# audio_mixer.net
KiCad netlist of a schematic drawn in EAGLE
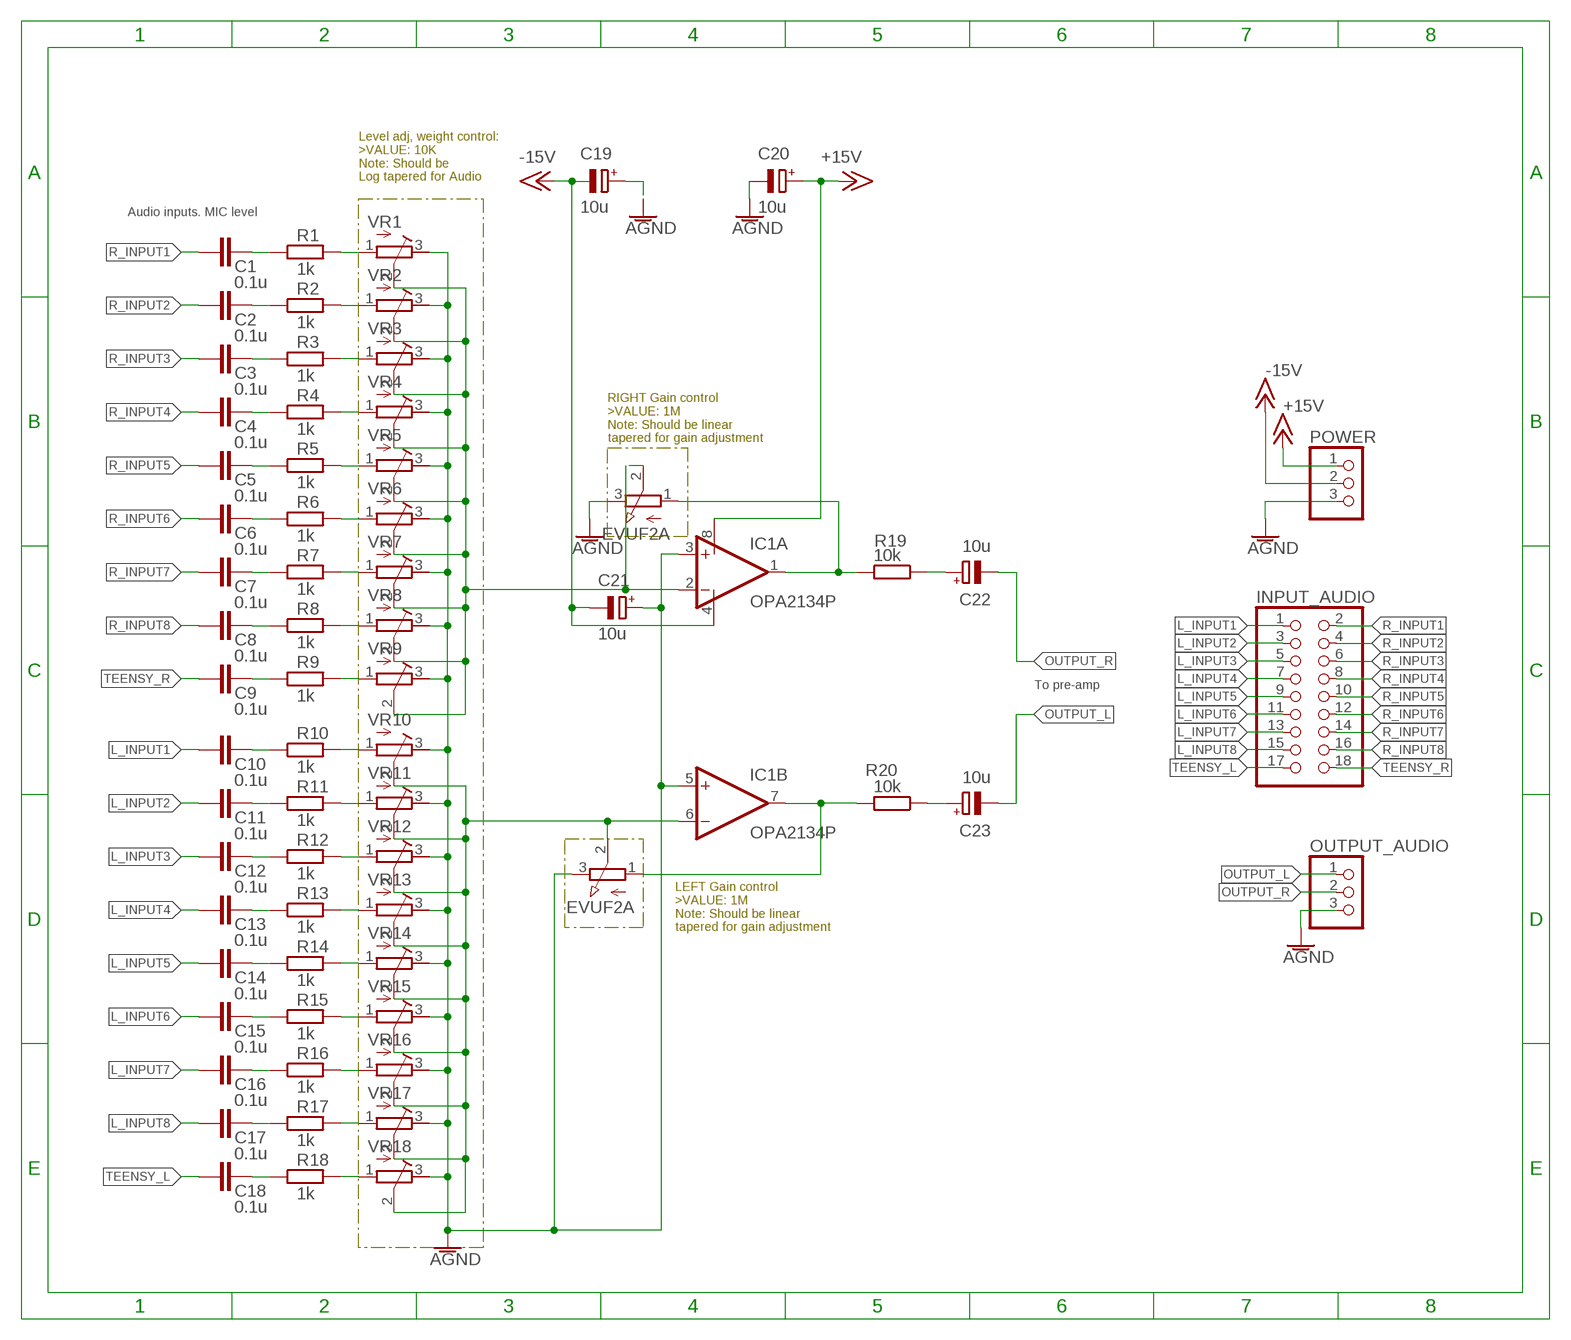
[diagram p0: schematic, sheet 1]

(export (version "E")
  (design (tool "Eeschema 10.0.6"))
  (components
    (comp (ref "C1")
      (value "0.1u")
      (footprint "eagle-import:C025-030X050")
      (libsource (lib "eagle-import") (part "C-EU025-030X050"))
    )
    (comp (ref "C2")
      (value "0.1u")
      (footprint "eagle-import:C025-030X050")
      (libsource (lib "eagle-import") (part "C-EU025-030X050"))
    )
    (comp (ref "C3")
      (value "0.1u")
      (footprint "eagle-import:C025-030X050")
      (libsource (lib "eagle-import") (part "C-EU025-030X050"))
    )
    (comp (ref "C4")
      (value "0.1u")
      (footprint "eagle-import:C025-030X050")
      (libsource (lib "eagle-import") (part "C-EU025-030X050"))
    )
    (comp (ref "C5")
      (value "0.1u")
      (footprint "eagle-import:C025-030X050")
      (libsource (lib "eagle-import") (part "C-EU025-030X050"))
    )
    (comp (ref "C6")
      (value "0.1u")
      (footprint "eagle-import:C025-030X050")
      (libsource (lib "eagle-import") (part "C-EU025-030X050"))
    )
    (comp (ref "C7")
      (value "0.1u")
      (footprint "eagle-import:C025-030X050")
      (libsource (lib "eagle-import") (part "C-EU025-030X050"))
    )
    (comp (ref "C8")
      (value "0.1u")
      (footprint "eagle-import:C025-030X050")
      (libsource (lib "eagle-import") (part "C-EU025-030X050"))
    )
    (comp (ref "C9")
      (value "0.1u")
      (footprint "eagle-import:C025-030X050")
      (libsource (lib "eagle-import") (part "C-EU025-030X050"))
    )
    (comp (ref "C10")
      (value "0.1u")
      (footprint "eagle-import:C025-030X050")
      (libsource (lib "eagle-import") (part "C-EU025-030X050"))
    )
    (comp (ref "C11")
      (value "0.1u")
      (footprint "eagle-import:C025-030X050")
      (libsource (lib "eagle-import") (part "C-EU025-030X050"))
    )
    (comp (ref "C12")
      (value "0.1u")
      (footprint "eagle-import:C025-030X050")
      (libsource (lib "eagle-import") (part "C-EU025-030X050"))
    )
    (comp (ref "C13")
      (value "0.1u")
      (footprint "eagle-import:C025-030X050")
      (libsource (lib "eagle-import") (part "C-EU025-030X050"))
    )
    (comp (ref "C14")
      (value "0.1u")
      (footprint "eagle-import:C025-030X050")
      (libsource (lib "eagle-import") (part "C-EU025-030X050"))
    )
    (comp (ref "C15")
      (value "0.1u")
      (footprint "eagle-import:C025-030X050")
      (libsource (lib "eagle-import") (part "C-EU025-030X050"))
    )
    (comp (ref "C16")
      (value "0.1u")
      (footprint "eagle-import:C025-030X050")
      (libsource (lib "eagle-import") (part "C-EU025-030X050"))
    )
    (comp (ref "C17")
      (value "0.1u")
      (footprint "eagle-import:C025-030X050")
      (libsource (lib "eagle-import") (part "C-EU025-030X050"))
    )
    (comp (ref "C18")
      (value "0.1u")
      (footprint "eagle-import:C025-030X050")
      (libsource (lib "eagle-import") (part "C-EU025-030X050"))
    )
    (comp (ref "C19")
      (value "10u")
      (footprint "eagle-import:E5-10,5")
      (libsource (lib "eagle-import") (part "CPOL-EUE5-10.5"))
    )
    (comp (ref "C20")
      (value "10u")
      (footprint "eagle-import:E5-10,5")
      (libsource (lib "eagle-import") (part "CPOL-EUE5-10.5"))
    )
    (comp (ref "C21")
      (value "10u")
      (footprint "eagle-import:E5-10,5")
      (libsource (lib "eagle-import") (part "CPOL-EUE5-10.5"))
    )
    (comp (ref "C22")
      (value "10u")
      (footprint "eagle-import:E5-10,5")
      (libsource (lib "eagle-import") (part "CPOL-EUE5-10.5"))
    )
    (comp (ref "C23")
      (value "10u")
      (footprint "eagle-import:E5-10,5")
      (libsource (lib "eagle-import") (part "CPOL-EUE5-10.5"))
    )
    (comp (ref "IC1")
      (value "OPA2134P")
      (footprint "eagle-import:DIL08")
      (libsource (lib "eagle-import") (part "OPA2134P"))
    )
    (comp (ref "INPUT_AUDIO")
      (value "PINHD-2X9")
      (footprint "eagle-import:2X09")
      (libsource (lib "eagle-import") (part "PINHD-2X9"))
    )
    (comp (ref "OUTPUT_AUDIO")
      (value "PINHD-1X3")
      (footprint "eagle-import:1X03")
      (libsource (lib "eagle-import") (part "PINHD-1X3"))
    )
    (comp (ref "POWER")
      (value "PINHD-1X3")
      (footprint "eagle-import:1X03")
      (libsource (lib "eagle-import") (part "PINHD-1X3"))
    )
    (comp (ref "R1")
      (value "1k")
      (footprint "eagle-import:R0805")
      (libsource (lib "eagle-import") (part "R-EU_R0805"))
    )
    (comp (ref "R2")
      (value "1k")
      (footprint "eagle-import:R0805")
      (libsource (lib "eagle-import") (part "R-EU_R0805"))
    )
    (comp (ref "R3")
      (value "1k")
      (footprint "eagle-import:R0805")
      (libsource (lib "eagle-import") (part "R-EU_R0805"))
    )
    (comp (ref "R4")
      (value "1k")
      (footprint "eagle-import:R0805")
      (libsource (lib "eagle-import") (part "R-EU_R0805"))
    )
    (comp (ref "R5")
      (value "1k")
      (footprint "eagle-import:R0805")
      (libsource (lib "eagle-import") (part "R-EU_R0805"))
    )
    (comp (ref "R6")
      (value "1k")
      (footprint "eagle-import:R0805")
      (libsource (lib "eagle-import") (part "R-EU_R0805"))
    )
    (comp (ref "R7")
      (value "1k")
      (footprint "eagle-import:R0805")
      (libsource (lib "eagle-import") (part "R-EU_R0805"))
    )
    (comp (ref "R8")
      (value "1k")
      (footprint "eagle-import:R0805")
      (libsource (lib "eagle-import") (part "R-EU_R0805"))
    )
    (comp (ref "R9")
      (value "1k")
      (footprint "eagle-import:R0805")
      (libsource (lib "eagle-import") (part "R-EU_R0805"))
    )
    (comp (ref "R10")
      (value "1k")
      (footprint "eagle-import:R0805")
      (libsource (lib "eagle-import") (part "R-EU_R0805"))
    )
    (comp (ref "R11")
      (value "1k")
      (footprint "eagle-import:R0805")
      (libsource (lib "eagle-import") (part "R-EU_R0805"))
    )
    (comp (ref "R12")
      (value "1k")
      (footprint "eagle-import:R0805")
      (libsource (lib "eagle-import") (part "R-EU_R0805"))
    )
    (comp (ref "R13")
      (value "1k")
      (footprint "eagle-import:R0805")
      (libsource (lib "eagle-import") (part "R-EU_R0805"))
    )
    (comp (ref "R14")
      (value "1k")
      (footprint "eagle-import:R0805")
      (libsource (lib "eagle-import") (part "R-EU_R0805"))
    )
    (comp (ref "R15")
      (value "1k")
      (footprint "eagle-import:R0805")
      (libsource (lib "eagle-import") (part "R-EU_R0805"))
    )
    (comp (ref "R16")
      (value "1k")
      (footprint "eagle-import:R0805")
      (libsource (lib "eagle-import") (part "R-EU_R0805"))
    )
    (comp (ref "R17")
      (value "1k")
      (footprint "eagle-import:R0805")
      (libsource (lib "eagle-import") (part "R-EU_R0805"))
    )
    (comp (ref "R18")
      (value "1k")
      (footprint "eagle-import:R0805")
      (libsource (lib "eagle-import") (part "R-EU_R0805"))
    )
    (comp (ref "R19")
      (value "10k")
      (footprint "eagle-import:R0805")
      (libsource (lib "eagle-import") (part "R-EU_R0805"))
    )
    (comp (ref "R20")
      (value "10k")
      (footprint "eagle-import:R0805")
      (libsource (lib "eagle-import") (part "R-EU_R0805"))
    )
    (comp (ref "VR1")
      (value "R-TRIMM3339P")
      (footprint "eagle-import:RTRIM3339P")
      (libsource (lib "eagle-import") (part "R-TRIMM3339P"))
    )
    (comp (ref "VR2")
      (value "R-TRIMM3339P")
      (footprint "eagle-import:RTRIM3339P")
      (libsource (lib "eagle-import") (part "R-TRIMM3339P"))
    )
    (comp (ref "VR3")
      (value "R-TRIMM3339P")
      (footprint "eagle-import:RTRIM3339P")
      (libsource (lib "eagle-import") (part "R-TRIMM3339P"))
    )
    (comp (ref "VR4")
      (value "R-TRIMM3339P")
      (footprint "eagle-import:RTRIM3339P")
      (libsource (lib "eagle-import") (part "R-TRIMM3339P"))
    )
    (comp (ref "VR5")
      (value "R-TRIMM3339P")
      (footprint "eagle-import:RTRIM3339P")
      (libsource (lib "eagle-import") (part "R-TRIMM3339P"))
    )
    (comp (ref "VR6")
      (value "R-TRIMM3339P")
      (footprint "eagle-import:RTRIM3339P")
      (libsource (lib "eagle-import") (part "R-TRIMM3339P"))
    )
    (comp (ref "VR7")
      (value "R-TRIMM3339P")
      (footprint "eagle-import:RTRIM3339P")
      (libsource (lib "eagle-import") (part "R-TRIMM3339P"))
    )
    (comp (ref "VR8")
      (value "R-TRIMM3339P")
      (footprint "eagle-import:RTRIM3339P")
      (libsource (lib "eagle-import") (part "R-TRIMM3339P"))
    )
    (comp (ref "VR9")
      (value "R-TRIMM3339P")
      (footprint "eagle-import:RTRIM3339P")
      (libsource (lib "eagle-import") (part "R-TRIMM3339P"))
    )
    (comp (ref "VR10")
      (value "R-TRIMM3339P")
      (footprint "eagle-import:RTRIM3339P")
      (libsource (lib "eagle-import") (part "R-TRIMM3339P"))
    )
    (comp (ref "VR11")
      (value "R-TRIMM3339P")
      (footprint "eagle-import:RTRIM3339P")
      (libsource (lib "eagle-import") (part "R-TRIMM3339P"))
    )
    (comp (ref "VR12")
      (value "R-TRIMM3339P")
      (footprint "eagle-import:RTRIM3339P")
      (libsource (lib "eagle-import") (part "R-TRIMM3339P"))
    )
    (comp (ref "VR13")
      (value "R-TRIMM3339P")
      (footprint "eagle-import:RTRIM3339P")
      (libsource (lib "eagle-import") (part "R-TRIMM3339P"))
    )
    (comp (ref "VR14")
      (value "R-TRIMM3339P")
      (footprint "eagle-import:RTRIM3339P")
      (libsource (lib "eagle-import") (part "R-TRIMM3339P"))
    )
    (comp (ref "VR15")
      (value "R-TRIMM3339P")
      (footprint "eagle-import:RTRIM3339P")
      (libsource (lib "eagle-import") (part "R-TRIMM3339P"))
    )
    (comp (ref "VR16")
      (value "R-TRIMM3339P")
      (footprint "eagle-import:RTRIM3339P")
      (libsource (lib "eagle-import") (part "R-TRIMM3339P"))
    )
    (comp (ref "VR17")
      (value "R-TRIMM3339P")
      (footprint "eagle-import:RTRIM3339P")
      (libsource (lib "eagle-import") (part "R-TRIMM3339P"))
    )
    (comp (ref "VR18")
      (value "R-TRIMM3339P")
      (footprint "eagle-import:RTRIM3339P")
      (libsource (lib "eagle-import") (part "R-TRIMM3339P"))
    )
    (comp (ref "VR19")
      (value "EVUF2A")
      (footprint "eagle-import:EVUF")
      (libsource (lib "eagle-import") (part "EVUAF2"))
    )
    (comp (ref "VR20")
      (value "EVUF2A")
      (footprint "eagle-import:EVUF")
      (libsource (lib "eagle-import") (part "EVUAF2"))
    )
  )
  (nets
    (net (code "1") (name "+15V") (class "Default")
      (node (ref "C20") (pin "+") (pinfunction "+_+") (pintype "passive"))
      (node (ref "IC1") (pin "8") (pinfunction "V+_8") (pintype "power_in"))
      (node (ref "POWER") (pin "1") (pinfunction "1_1") (pintype "passive"))
    )
    (net (code "2") (name "-15V") (class "Default")
      (node (ref "C19") (pin "-") (pinfunction "-_-") (pintype "passive"))
      (node (ref "C21") (pin "-") (pinfunction "-_-") (pintype "passive"))
      (node (ref "IC1") (pin "4") (pinfunction "V-_4") (pintype "power_in"))
      (node (ref "POWER") (pin "2") (pinfunction "2_2") (pintype "passive"))
    )
    (net (code "3") (name "AGND") (class "Default")
      (node (ref "C19") (pin "+") (pinfunction "+_+") (pintype "passive"))
      (node (ref "C20") (pin "-") (pinfunction "-_-") (pintype "passive"))
      (node (ref "C21") (pin "+") (pinfunction "+_+") (pintype "passive"))
      (node (ref "IC1") (pin "3") (pinfunction "+IN_3") (pintype "input"))
      (node (ref "IC1") (pin "5") (pinfunction "+IN_5") (pintype "input"))
      (node (ref "OUTPUT_AUDIO") (pin "3") (pinfunction "3_3") (pintype "passive"))
      (node (ref "POWER") (pin "3") (pinfunction "3_3") (pintype "passive"))
      (node (ref "VR1") (pin "3") (pinfunction "E_3") (pintype "passive"))
      (node (ref "VR10") (pin "3") (pinfunction "E_3") (pintype "passive"))
      (node (ref "VR11") (pin "3") (pinfunction "E_3") (pintype "passive"))
      (node (ref "VR12") (pin "3") (pinfunction "E_3") (pintype "passive"))
      (node (ref "VR13") (pin "3") (pinfunction "E_3") (pintype "passive"))
      (node (ref "VR14") (pin "3") (pinfunction "E_3") (pintype "passive"))
      (node (ref "VR15") (pin "3") (pinfunction "E_3") (pintype "passive"))
      (node (ref "VR16") (pin "3") (pinfunction "E_3") (pintype "passive"))
      (node (ref "VR17") (pin "3") (pinfunction "E_3") (pintype "passive"))
      (node (ref "VR18") (pin "3") (pinfunction "E_3") (pintype "passive"))
      (node (ref "VR19") (pin "3") (pinfunction "E_3") (pintype "passive"))
      (node (ref "VR2") (pin "3") (pinfunction "E_3") (pintype "passive"))
      (node (ref "VR20") (pin "3") (pinfunction "E_3") (pintype "passive"))
      (node (ref "VR3") (pin "3") (pinfunction "E_3") (pintype "passive"))
      (node (ref "VR4") (pin "3") (pinfunction "E_3") (pintype "passive"))
      (node (ref "VR5") (pin "3") (pinfunction "E_3") (pintype "passive"))
      (node (ref "VR6") (pin "3") (pinfunction "E_3") (pintype "passive"))
      (node (ref "VR7") (pin "3") (pinfunction "E_3") (pintype "passive"))
      (node (ref "VR8") (pin "3") (pinfunction "E_3") (pintype "passive"))
      (node (ref "VR9") (pin "3") (pinfunction "E_3") (pintype "passive"))
    )
    (net (code "4") (name "L_INPUT1") (class "Default")
      (node (ref "C10") (pin "2") (pinfunction "2_2") (pintype "passive"))
      (node (ref "INPUT_AUDIO") (pin "1") (pinfunction "1_1") (pintype "passive"))
    )
    (net (code "5") (name "L_INPUT2") (class "Default")
      (node (ref "C11") (pin "2") (pinfunction "2_2") (pintype "passive"))
      (node (ref "INPUT_AUDIO") (pin "3") (pinfunction "3_3") (pintype "passive"))
    )
    (net (code "6") (name "L_INPUT3") (class "Default")
      (node (ref "C12") (pin "2") (pinfunction "2_2") (pintype "passive"))
      (node (ref "INPUT_AUDIO") (pin "5") (pinfunction "5_5") (pintype "passive"))
    )
    (net (code "7") (name "L_INPUT4") (class "Default")
      (node (ref "C13") (pin "2") (pinfunction "2_2") (pintype "passive"))
      (node (ref "INPUT_AUDIO") (pin "7") (pinfunction "7_7") (pintype "passive"))
    )
    (net (code "8") (name "L_INPUT5") (class "Default")
      (node (ref "C14") (pin "2") (pinfunction "2_2") (pintype "passive"))
      (node (ref "INPUT_AUDIO") (pin "9") (pinfunction "9_9") (pintype "passive"))
    )
    (net (code "9") (name "L_INPUT6") (class "Default")
      (node (ref "C15") (pin "2") (pinfunction "2_2") (pintype "passive"))
      (node (ref "INPUT_AUDIO") (pin "11") (pinfunction "11_11") (pintype "passive"))
    )
    (net (code "10") (name "L_INPUT7") (class "Default")
      (node (ref "C16") (pin "2") (pinfunction "2_2") (pintype "passive"))
      (node (ref "INPUT_AUDIO") (pin "13") (pinfunction "13_13") (pintype "passive"))
    )
    (net (code "11") (name "L_INPUT8") (class "Default")
      (node (ref "C17") (pin "2") (pinfunction "2_2") (pintype "passive"))
      (node (ref "INPUT_AUDIO") (pin "15") (pinfunction "15_15") (pintype "passive"))
    )
    (net (code "12") (name "Net-(C1-Pad1)") (class "Default")
      (node (ref "C1") (pin "1") (pinfunction "1_1") (pintype "passive"))
      (node (ref "R1") (pin "1") (pinfunction "1_1") (pintype "passive"))
    )
    (net (code "13") (name "Net-(C2-Pad1)") (class "Default")
      (node (ref "C2") (pin "1") (pinfunction "1_1") (pintype "passive"))
      (node (ref "R2") (pin "1") (pinfunction "1_1") (pintype "passive"))
    )
    (net (code "14") (name "Net-(C3-Pad1)") (class "Default")
      (node (ref "C3") (pin "1") (pinfunction "1_1") (pintype "passive"))
      (node (ref "R3") (pin "1") (pinfunction "1_1") (pintype "passive"))
    )
    (net (code "15") (name "Net-(C4-Pad1)") (class "Default")
      (node (ref "C4") (pin "1") (pinfunction "1_1") (pintype "passive"))
      (node (ref "R4") (pin "1") (pinfunction "1_1") (pintype "passive"))
    )
    (net (code "16") (name "Net-(C5-Pad1)") (class "Default")
      (node (ref "C5") (pin "1") (pinfunction "1_1") (pintype "passive"))
      (node (ref "R5") (pin "1") (pinfunction "1_1") (pintype "passive"))
    )
    (net (code "17") (name "Net-(C6-Pad1)") (class "Default")
      (node (ref "C6") (pin "1") (pinfunction "1_1") (pintype "passive"))
      (node (ref "R6") (pin "1") (pinfunction "1_1") (pintype "passive"))
    )
    (net (code "18") (name "Net-(C7-Pad1)") (class "Default")
      (node (ref "C7") (pin "1") (pinfunction "1_1") (pintype "passive"))
      (node (ref "R7") (pin "1") (pinfunction "1_1") (pintype "passive"))
    )
    (net (code "19") (name "Net-(C8-Pad1)") (class "Default")
      (node (ref "C8") (pin "1") (pinfunction "1_1") (pintype "passive"))
      (node (ref "R8") (pin "1") (pinfunction "1_1") (pintype "passive"))
    )
    (net (code "20") (name "Net-(C9-Pad1)") (class "Default")
      (node (ref "C9") (pin "1") (pinfunction "1_1") (pintype "passive"))
      (node (ref "R9") (pin "1") (pinfunction "1_1") (pintype "passive"))
    )
    (net (code "21") (name "Net-(C10-Pad1)") (class "Default")
      (node (ref "C10") (pin "1") (pinfunction "1_1") (pintype "passive"))
      (node (ref "R10") (pin "1") (pinfunction "1_1") (pintype "passive"))
    )
    (net (code "22") (name "Net-(C11-Pad1)") (class "Default")
      (node (ref "C11") (pin "1") (pinfunction "1_1") (pintype "passive"))
      (node (ref "R11") (pin "1") (pinfunction "1_1") (pintype "passive"))
    )
    (net (code "23") (name "Net-(C12-Pad1)") (class "Default")
      (node (ref "C12") (pin "1") (pinfunction "1_1") (pintype "passive"))
      (node (ref "R12") (pin "1") (pinfunction "1_1") (pintype "passive"))
    )
    (net (code "24") (name "Net-(C13-Pad1)") (class "Default")
      (node (ref "C13") (pin "1") (pinfunction "1_1") (pintype "passive"))
      (node (ref "R13") (pin "1") (pinfunction "1_1") (pintype "passive"))
    )
    (net (code "25") (name "Net-(C14-Pad1)") (class "Default")
      (node (ref "C14") (pin "1") (pinfunction "1_1") (pintype "passive"))
      (node (ref "R14") (pin "1") (pinfunction "1_1") (pintype "passive"))
    )
    (net (code "26") (name "Net-(C15-Pad1)") (class "Default")
      (node (ref "C15") (pin "1") (pinfunction "1_1") (pintype "passive"))
      (node (ref "R15") (pin "1") (pinfunction "1_1") (pintype "passive"))
    )
    (net (code "27") (name "Net-(C16-Pad1)") (class "Default")
      (node (ref "C16") (pin "1") (pinfunction "1_1") (pintype "passive"))
      (node (ref "R16") (pin "1") (pinfunction "1_1") (pintype "passive"))
    )
    (net (code "28") (name "Net-(C17-Pad1)") (class "Default")
      (node (ref "C17") (pin "1") (pinfunction "1_1") (pintype "passive"))
      (node (ref "R17") (pin "1") (pinfunction "1_1") (pintype "passive"))
    )
    (net (code "29") (name "Net-(C18-Pad1)") (class "Default")
      (node (ref "C18") (pin "1") (pinfunction "1_1") (pintype "passive"))
      (node (ref "R18") (pin "1") (pinfunction "1_1") (pintype "passive"))
    )
    (net (code "30") (name "Net-(C22-Pad+)") (class "Default")
      (node (ref "C22") (pin "+") (pinfunction "+_+") (pintype "passive"))
      (node (ref "R19") (pin "1") (pinfunction "1_1") (pintype "passive"))
    )
    (net (code "31") (name "Net-(C23-Pad+)") (class "Default")
      (node (ref "C23") (pin "+") (pinfunction "+_+") (pintype "passive"))
      (node (ref "R20") (pin "1") (pinfunction "1_1") (pintype "passive"))
    )
    (net (code "32") (name "Net-(IC1A--IN)") (class "Default")
      (node (ref "IC1") (pin "2") (pinfunction "-IN_2") (pintype "input"))
      (node (ref "VR1") (pin "2") (pinfunction "S_2") (pintype "passive"))
      (node (ref "VR19") (pin "2") (pinfunction "S_2") (pintype "passive"))
      (node (ref "VR2") (pin "2") (pinfunction "S_2") (pintype "passive"))
      (node (ref "VR3") (pin "2") (pinfunction "S_2") (pintype "passive"))
      (node (ref "VR4") (pin "2") (pinfunction "S_2") (pintype "passive"))
      (node (ref "VR5") (pin "2") (pinfunction "S_2") (pintype "passive"))
      (node (ref "VR6") (pin "2") (pinfunction "S_2") (pintype "passive"))
      (node (ref "VR7") (pin "2") (pinfunction "S_2") (pintype "passive"))
      (node (ref "VR8") (pin "2") (pinfunction "S_2") (pintype "passive"))
      (node (ref "VR9") (pin "2") (pinfunction "S_2") (pintype "passive"))
    )
    (net (code "33") (name "Net-(IC1A-OUT)") (class "Default")
      (node (ref "IC1") (pin "1") (pinfunction "OUT_1") (pintype "output"))
      (node (ref "R19") (pin "2") (pinfunction "2_2") (pintype "passive"))
      (node (ref "VR19") (pin "1") (pinfunction "A_1") (pintype "passive"))
    )
    (net (code "34") (name "Net-(IC1B--IN)") (class "Default")
      (node (ref "IC1") (pin "6") (pinfunction "-IN_6") (pintype "input"))
      (node (ref "VR10") (pin "2") (pinfunction "S_2") (pintype "passive"))
      (node (ref "VR11") (pin "2") (pinfunction "S_2") (pintype "passive"))
      (node (ref "VR12") (pin "2") (pinfunction "S_2") (pintype "passive"))
      (node (ref "VR13") (pin "2") (pinfunction "S_2") (pintype "passive"))
      (node (ref "VR14") (pin "2") (pinfunction "S_2") (pintype "passive"))
      (node (ref "VR15") (pin "2") (pinfunction "S_2") (pintype "passive"))
      (node (ref "VR16") (pin "2") (pinfunction "S_2") (pintype "passive"))
      (node (ref "VR17") (pin "2") (pinfunction "S_2") (pintype "passive"))
      (node (ref "VR18") (pin "2") (pinfunction "S_2") (pintype "passive"))
      (node (ref "VR20") (pin "2") (pinfunction "S_2") (pintype "passive"))
    )
    (net (code "35") (name "Net-(IC1B-OUT)") (class "Default")
      (node (ref "IC1") (pin "7") (pinfunction "OUT_7") (pintype "output"))
      (node (ref "R20") (pin "2") (pinfunction "2_2") (pintype "passive"))
      (node (ref "VR20") (pin "1") (pinfunction "A_1") (pintype "passive"))
    )
    (net (code "36") (name "Net-(VR1-A)") (class "Default")
      (node (ref "R1") (pin "2") (pinfunction "2_2") (pintype "passive"))
      (node (ref "VR1") (pin "1") (pinfunction "A_1") (pintype "passive"))
    )
    (net (code "37") (name "Net-(VR2-A)") (class "Default")
      (node (ref "R2") (pin "2") (pinfunction "2_2") (pintype "passive"))
      (node (ref "VR2") (pin "1") (pinfunction "A_1") (pintype "passive"))
    )
    (net (code "38") (name "Net-(VR3-A)") (class "Default")
      (node (ref "R3") (pin "2") (pinfunction "2_2") (pintype "passive"))
      (node (ref "VR3") (pin "1") (pinfunction "A_1") (pintype "passive"))
    )
    (net (code "39") (name "Net-(VR4-A)") (class "Default")
      (node (ref "R4") (pin "2") (pinfunction "2_2") (pintype "passive"))
      (node (ref "VR4") (pin "1") (pinfunction "A_1") (pintype "passive"))
    )
    (net (code "40") (name "Net-(VR5-A)") (class "Default")
      (node (ref "R5") (pin "2") (pinfunction "2_2") (pintype "passive"))
      (node (ref "VR5") (pin "1") (pinfunction "A_1") (pintype "passive"))
    )
    (net (code "41") (name "Net-(VR6-A)") (class "Default")
      (node (ref "R6") (pin "2") (pinfunction "2_2") (pintype "passive"))
      (node (ref "VR6") (pin "1") (pinfunction "A_1") (pintype "passive"))
    )
    (net (code "42") (name "Net-(VR7-A)") (class "Default")
      (node (ref "R7") (pin "2") (pinfunction "2_2") (pintype "passive"))
      (node (ref "VR7") (pin "1") (pinfunction "A_1") (pintype "passive"))
    )
    (net (code "43") (name "Net-(VR8-A)") (class "Default")
      (node (ref "R8") (pin "2") (pinfunction "2_2") (pintype "passive"))
      (node (ref "VR8") (pin "1") (pinfunction "A_1") (pintype "passive"))
    )
    (net (code "44") (name "Net-(VR9-A)") (class "Default")
      (node (ref "R9") (pin "2") (pinfunction "2_2") (pintype "passive"))
      (node (ref "VR9") (pin "1") (pinfunction "A_1") (pintype "passive"))
    )
    (net (code "45") (name "Net-(VR10-A)") (class "Default")
      (node (ref "R10") (pin "2") (pinfunction "2_2") (pintype "passive"))
      (node (ref "VR10") (pin "1") (pinfunction "A_1") (pintype "passive"))
    )
    (net (code "46") (name "Net-(VR11-A)") (class "Default")
      (node (ref "R11") (pin "2") (pinfunction "2_2") (pintype "passive"))
      (node (ref "VR11") (pin "1") (pinfunction "A_1") (pintype "passive"))
    )
    (net (code "47") (name "Net-(VR12-A)") (class "Default")
      (node (ref "R12") (pin "2") (pinfunction "2_2") (pintype "passive"))
      (node (ref "VR12") (pin "1") (pinfunction "A_1") (pintype "passive"))
    )
    (net (code "48") (name "Net-(VR13-A)") (class "Default")
      (node (ref "R13") (pin "2") (pinfunction "2_2") (pintype "passive"))
      (node (ref "VR13") (pin "1") (pinfunction "A_1") (pintype "passive"))
    )
    (net (code "49") (name "Net-(VR14-A)") (class "Default")
      (node (ref "R14") (pin "2") (pinfunction "2_2") (pintype "passive"))
      (node (ref "VR14") (pin "1") (pinfunction "A_1") (pintype "passive"))
    )
    (net (code "50") (name "Net-(VR15-A)") (class "Default")
      (node (ref "R15") (pin "2") (pinfunction "2_2") (pintype "passive"))
      (node (ref "VR15") (pin "1") (pinfunction "A_1") (pintype "passive"))
    )
    (net (code "51") (name "Net-(VR16-A)") (class "Default")
      (node (ref "R16") (pin "2") (pinfunction "2_2") (pintype "passive"))
      (node (ref "VR16") (pin "1") (pinfunction "A_1") (pintype "passive"))
    )
    (net (code "52") (name "Net-(VR17-A)") (class "Default")
      (node (ref "R17") (pin "2") (pinfunction "2_2") (pintype "passive"))
      (node (ref "VR17") (pin "1") (pinfunction "A_1") (pintype "passive"))
    )
    (net (code "53") (name "Net-(VR18-A)") (class "Default")
      (node (ref "R18") (pin "2") (pinfunction "2_2") (pintype "passive"))
      (node (ref "VR18") (pin "1") (pinfunction "A_1") (pintype "passive"))
    )
    (net (code "54") (name "OUTPUT_L") (class "Default")
      (node (ref "C23") (pin "-") (pinfunction "-_-") (pintype "passive"))
      (node (ref "OUTPUT_AUDIO") (pin "1") (pinfunction "1_1") (pintype "passive"))
    )
    (net (code "55") (name "OUTPUT_R") (class "Default")
      (node (ref "C22") (pin "-") (pinfunction "-_-") (pintype "passive"))
      (node (ref "OUTPUT_AUDIO") (pin "2") (pinfunction "2_2") (pintype "passive"))
    )
    (net (code "56") (name "R_INPUT1") (class "Default")
      (node (ref "C1") (pin "2") (pinfunction "2_2") (pintype "passive"))
      (node (ref "INPUT_AUDIO") (pin "2") (pinfunction "2_2") (pintype "passive"))
    )
    (net (code "57") (name "R_INPUT2") (class "Default")
      (node (ref "C2") (pin "2") (pinfunction "2_2") (pintype "passive"))
      (node (ref "INPUT_AUDIO") (pin "4") (pinfunction "4_4") (pintype "passive"))
    )
    (net (code "58") (name "R_INPUT3") (class "Default")
      (node (ref "C3") (pin "2") (pinfunction "2_2") (pintype "passive"))
      (node (ref "INPUT_AUDIO") (pin "6") (pinfunction "6_6") (pintype "passive"))
    )
    (net (code "59") (name "R_INPUT4") (class "Default")
      (node (ref "C4") (pin "2") (pinfunction "2_2") (pintype "passive"))
      (node (ref "INPUT_AUDIO") (pin "8") (pinfunction "8_8") (pintype "passive"))
    )
    (net (code "60") (name "R_INPUT5") (class "Default")
      (node (ref "C5") (pin "2") (pinfunction "2_2") (pintype "passive"))
      (node (ref "INPUT_AUDIO") (pin "10") (pinfunction "10_10") (pintype "passive"))
    )
    (net (code "61") (name "R_INPUT6") (class "Default")
      (node (ref "C6") (pin "2") (pinfunction "2_2") (pintype "passive"))
      (node (ref "INPUT_AUDIO") (pin "12") (pinfunction "12_12") (pintype "passive"))
    )
    (net (code "62") (name "R_INPUT7") (class "Default")
      (node (ref "C7") (pin "2") (pinfunction "2_2") (pintype "passive"))
      (node (ref "INPUT_AUDIO") (pin "14") (pinfunction "14_14") (pintype "passive"))
    )
    (net (code "63") (name "R_INPUT8") (class "Default")
      (node (ref "C8") (pin "2") (pinfunction "2_2") (pintype "passive"))
      (node (ref "INPUT_AUDIO") (pin "16") (pinfunction "16_16") (pintype "passive"))
    )
    (net (code "64") (name "TEENSY_L") (class "Default")
      (node (ref "C18") (pin "2") (pinfunction "2_2") (pintype "passive"))
      (node (ref "INPUT_AUDIO") (pin "17") (pinfunction "17_17") (pintype "passive"))
    )
    (net (code "65") (name "TEENSY_R") (class "Default")
      (node (ref "C9") (pin "2") (pinfunction "2_2") (pintype "passive"))
      (node (ref "INPUT_AUDIO") (pin "18") (pinfunction "18_18") (pintype "passive"))
    )
  )
)
